# Top.net
KiCad netlist of a schematic drawn in Altium Designer
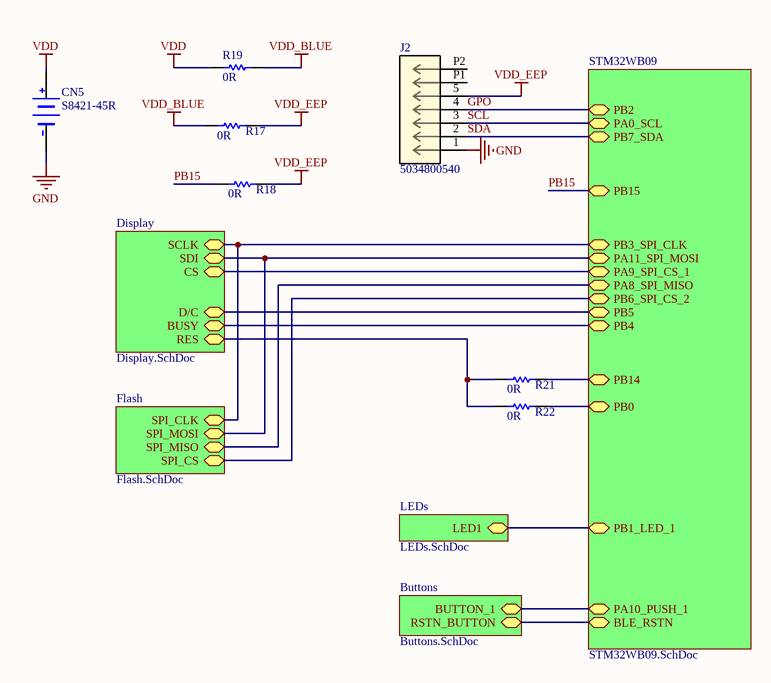
[diagram p0: Top.SchDoc]

(export (version "E")
  (design (tool "Eeschema 10.0.6"))
  (components
    (comp (ref "CN5")
      (value "S8421-45R")
      (footprint "BAT_HARWIN_S8421-45R_CR2032_SMD_2P")
      (description "CR2032 compact battery holder")
      (fields (field (name "INTERNAL_PART_NUMBER") "MCD-02936") (field (name "MANUFACTURER") "HARWIN"))
      (libsource (lib "MCD_PARTS_database") (part "BATTERY HOLDER"))
    )
    (comp (ref "J2")
      (value "5034800540")
      (footprint "CON_5034800540_MOL")
      (description "No Description Available")
      (fields
        (field (name "MANUFACTURER") "Molex")
        (field (name "COPYRIGHT") "Copyright (C) 2023 Ultra Librarian. All rights reserved.")
      )
      (libsource (lib "missing_parts") (part "5034800540_5_circuits"))
    )
    (comp (ref "R17")
      (value "0R")
      (footprint "R0402")
      (description "Resistor, 0R, 0402, +/-5%, 1/16W")
      (fields (field (name "INTERNAL_PART_NUMBER") "MCD-00052") (field (name "MANUFACTURER") "YAGEO"))
      (libsource (lib "MCD_PARTS_database") (part "Resistor"))
    )
    (comp (ref "R18")
      (value "0R")
      (footprint "R0402")
      (description "Resistor, 0R, 0402, +/-5%, 1/16W")
      (fields (field (name "INTERNAL_PART_NUMBER") "MCD-00052") (field (name "MANUFACTURER") "YAGEO"))
      (libsource (lib "MCD_PARTS_database") (part "Resistor"))
    )
    (comp (ref "R19")
      (value "0R")
      (footprint "R0603")
      (description "Resistor, 0R, 0603, +/- 0.5mR, 1/4W")
      (fields
        (field (name "INTERNAL_PART_NUMBER") "MCD-00181")
        (field (name "MANUFACTURER") "ROHM SEMICONDUCTOR")
      )
      (libsource (lib "MCD_PARTS_database") (part "Resistor"))
    )
    (comp (ref "R21")
      (value "0R")
      (footprint "R0402")
      (description "Resistor, 0R, 0402, +/-5%, 1/16W")
      (fields (field (name "INTERNAL_PART_NUMBER") "MCD-00052") (field (name "MANUFACTURER") "YAGEO"))
      (libsource (lib "MCD_PARTS_database") (part "Resistor"))
    )
    (comp (ref "R22")
      (value "0R")
      (footprint "R0402")
      (description "Resistor, 0R, 0402, +/-5%, 1/16W")
      (fields (field (name "INTERNAL_PART_NUMBER") "MCD-00052") (field (name "MANUFACTURER") "YAGEO"))
      (libsource (lib "MCD_PARTS_database") (part "Resistor"))
    )
  )
  (nets
    (net (code "6") (name "/GPO") (class "Default")
      (node (ref "J2") (pin "4") (pinfunction "4_4") (pintype "passive"))
    )
    (net (code "10") (name "/PB0") (class "Default")
      (node (ref "R22") (pin "2") (pinfunction "2_2") (pintype "passive"))
    )
    (net (code "13") (name "/PB14") (class "Default")
      (node (ref "R21") (pin "2") (pinfunction "2_2") (pintype "passive"))
    )
    (net (code "14") (name "/PB15") (class "Default")
      (node (ref "R18") (pin "1") (pinfunction "1_1") (pintype "passive"))
    )
    (net (code "15") (name "/RES") (class "Default")
      (node (ref "R21") (pin "1") (pinfunction "1_1") (pintype "passive"))
      (node (ref "R22") (pin "1") (pinfunction "1_1") (pintype "passive"))
    )
    (net (code "16") (name "/SCL") (class "Default")
      (node (ref "J2") (pin "3") (pinfunction "3_3") (pintype "passive"))
    )
    (net (code "17") (name "/SDA") (class "Default")
      (node (ref "J2") (pin "2") (pinfunction "2_2") (pintype "passive"))
    )
    (net (code "18") (name "GND") (class "Default")
      (node (ref "CN5") (pin "2") (pinfunction "-_2") (pintype "passive"))
      (node (ref "J2") (pin "1") (pinfunction "1_1") (pintype "passive"))
    )
    (net (code "19") (name "VDD") (class "Default")
      (node (ref "CN5") (pin "1") (pinfunction "+_1") (pintype "passive"))
      (node (ref "R19") (pin "1") (pinfunction "1_1") (pintype "passive"))
    )
    (net (code "20") (name "VDD_BLUE") (class "Default")
      (node (ref "R17") (pin "1") (pinfunction "1_1") (pintype "passive"))
      (node (ref "R19") (pin "2") (pinfunction "2_2") (pintype "passive"))
    )
    (net (code "21") (name "VDD_EEP") (class "Default")
      (node (ref "J2") (pin "5") (pinfunction "5_5") (pintype "passive"))
      (node (ref "R17") (pin "2") (pinfunction "2_2") (pintype "passive"))
      (node (ref "R18") (pin "2") (pinfunction "2_2") (pintype "passive"))
    )
    (net (code "22") (name "unconnected-(J2-PadP1)") (class "Default")
      (node (ref "J2") (pin "P1") (pinfunction "P1_P1") (pintype "passive"))
    )
    (net (code "23") (name "unconnected-(J2-PadP2)") (class "Default")
      (node (ref "J2") (pin "P2") (pinfunction "P2_P2") (pintype "passive"))
    )
  )
)
